# 18650Charger.net
KiCad netlist of a schematic drawn in EasyEDA Pro
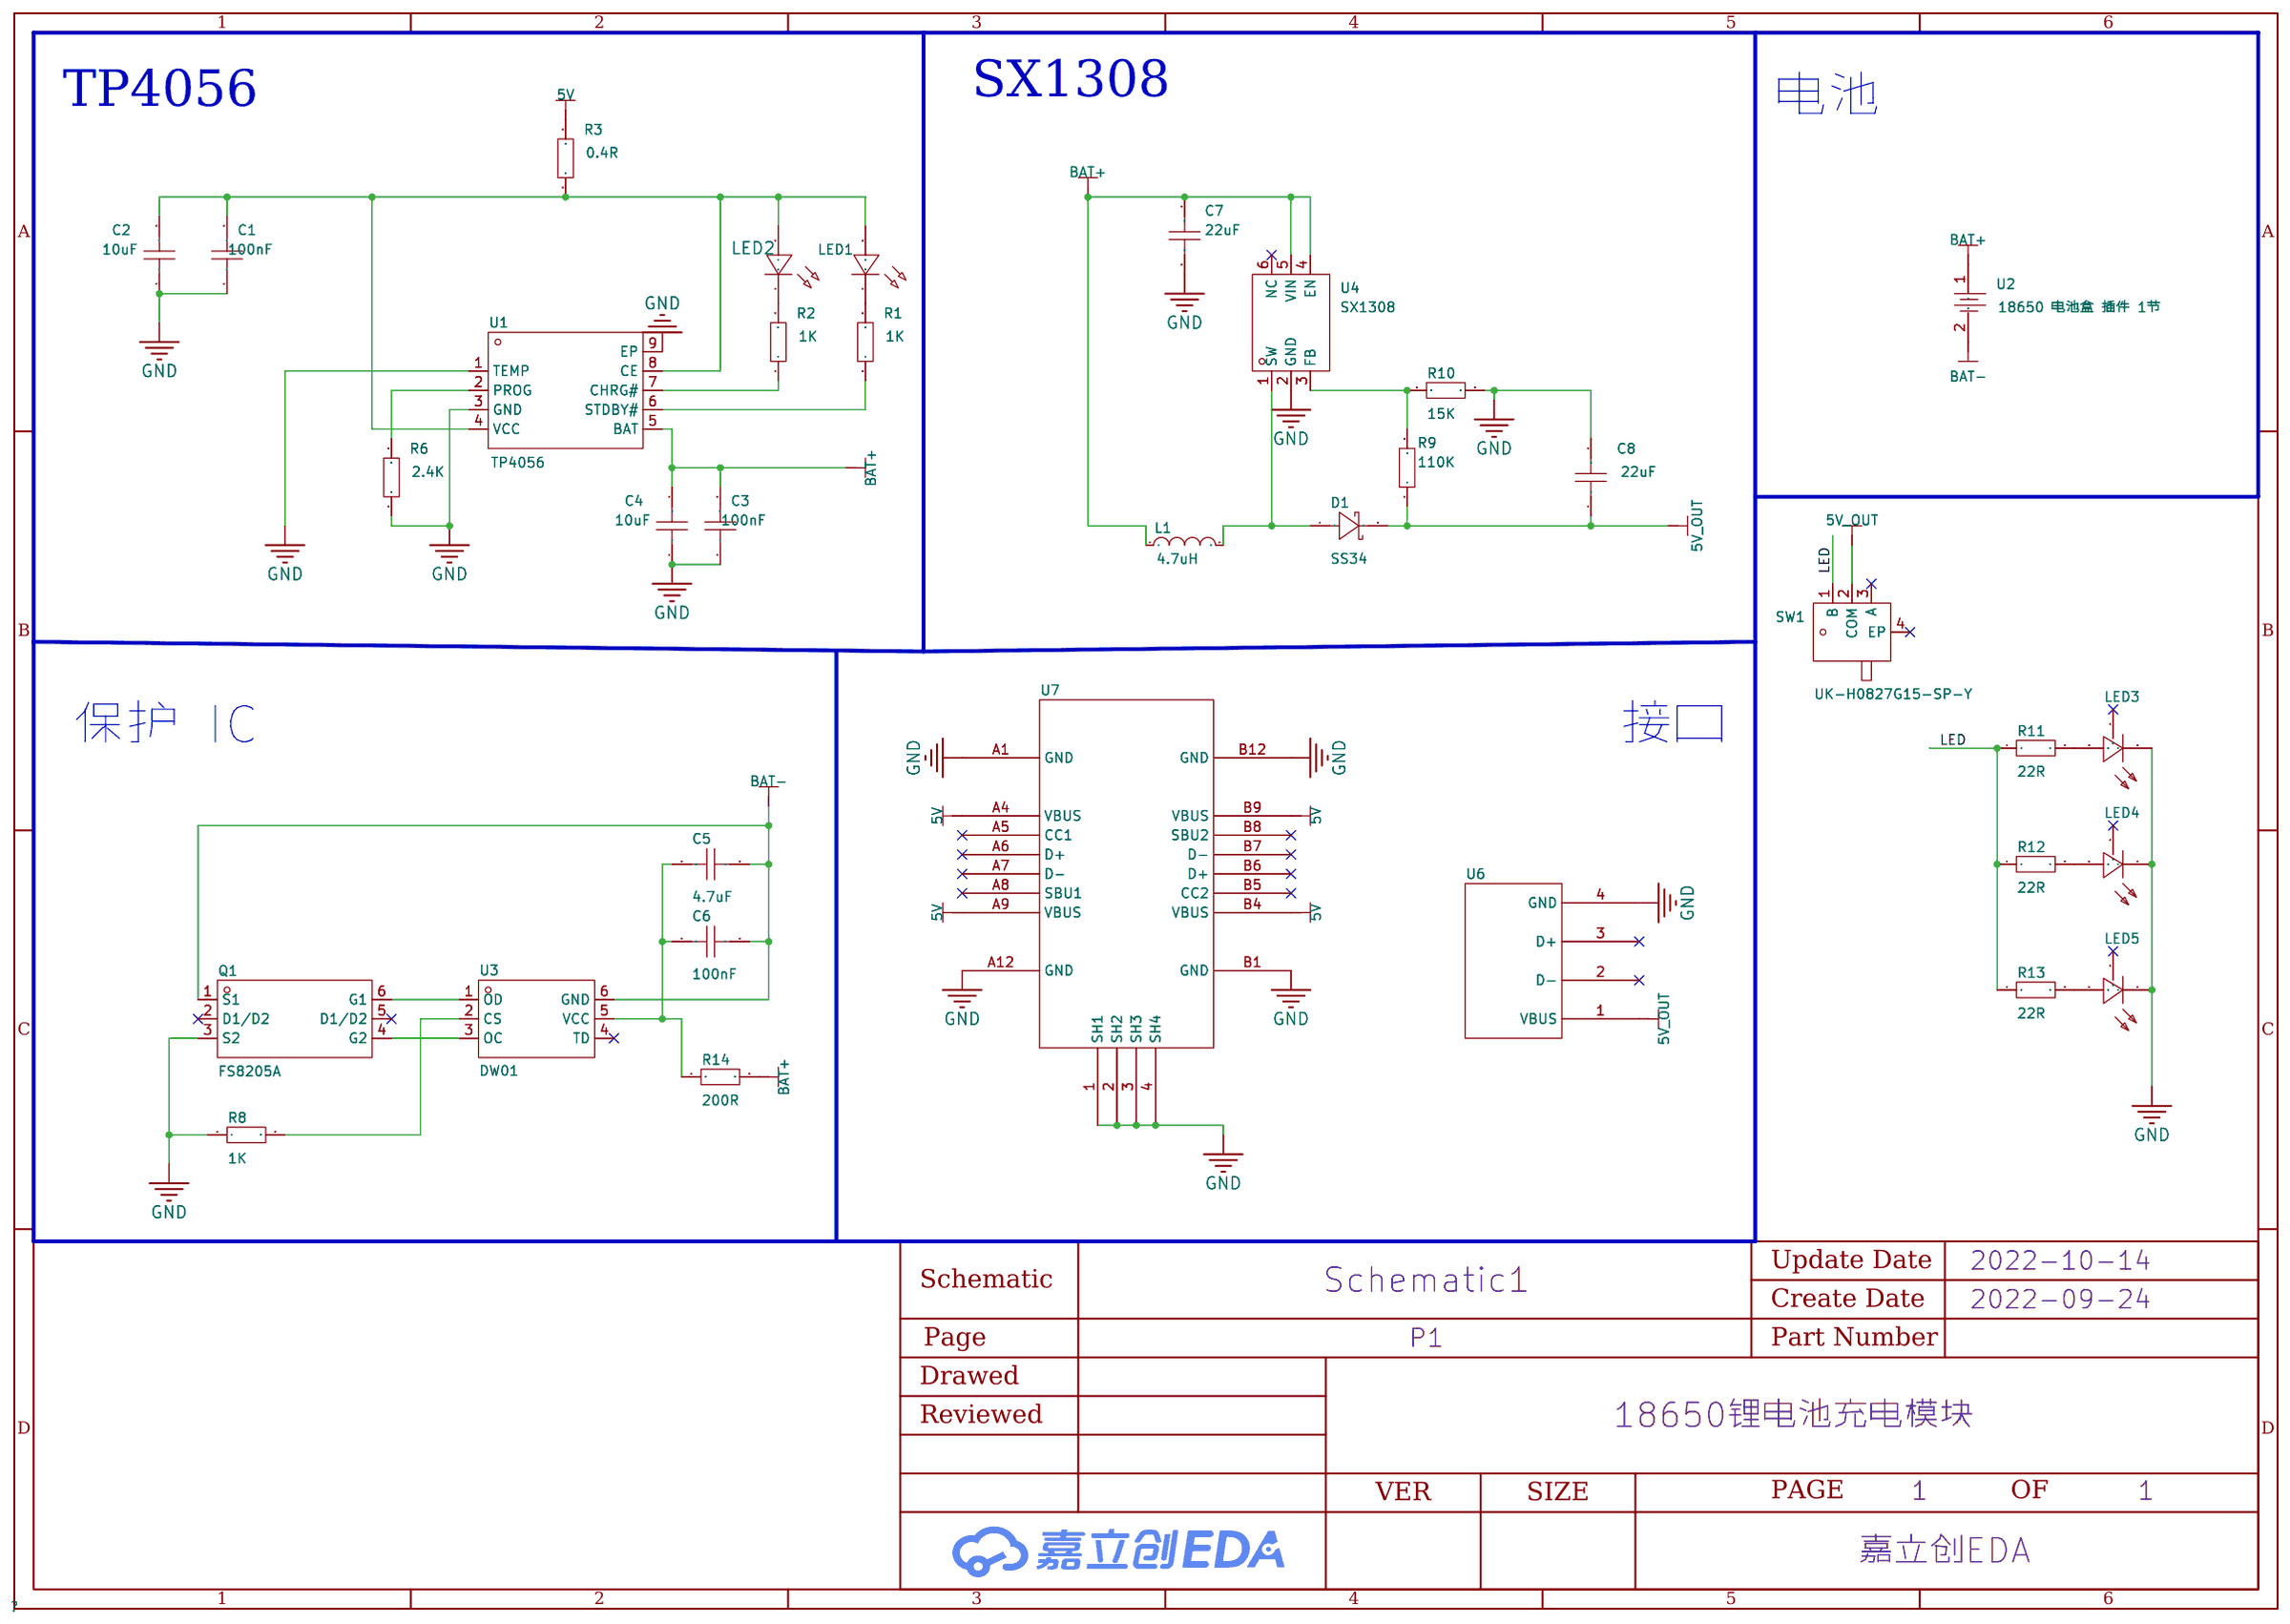
[diagram p0: schematic sheet]

(export (version "E")
  (design (tool "Eeschema 10.0.6"))
  (components
    (comp (ref "C1")
      (value "100nF")
      (footprint "easyedapro:C0805")
      (description "容值:100nF;精度:±10%;额定电压:50V;温度系数:X7R;")
      (libsource (lib "easyedapro") (part "C1210X7R475K630NT"))
    )
    (comp (ref "C2")
      (value "100nF")
      (footprint "easyedapro:C0805")
      (description "容值:100nF;精度:±10%;额定电压:50V;温度系数:X7R;")
      (libsource (lib "easyedapro") (part "C1210X7R475K630NT"))
    )
    (comp (ref "C3")
      (value "100nF")
      (footprint "easyedapro:C0805")
      (description "容值:100nF;精度:±10%;额定电压:50V;温度系数:X7R;")
      (libsource (lib "easyedapro") (part "C1210X7R475K630NT"))
    )
    (comp (ref "C4")
      (value "100nF")
      (footprint "easyedapro:C0805")
      (description "容值:100nF;精度:±10%;额定电压:50V;温度系数:X7R;")
      (libsource (lib "easyedapro") (part "C1210X7R475K630NT"))
    )
    (comp (ref "C5")
      (value "100nF")
      (footprint "easyedapro:C0805")
      (description "容值:100nF;精度:±10%;额定电压:50V;温度系数:X7R;")
      (libsource (lib "easyedapro") (part "C1210X7R475K630NT"))
    )
    (comp (ref "C6")
      (value "100nF")
      (footprint "easyedapro:C0805")
      (description "容值:100nF;精度:±10%;额定电压:50V;温度系数:X7R;")
      (libsource (lib "easyedapro") (part "C1210X7R475K630NT"))
    )
    (comp (ref "C7")
      (value "100nF")
      (footprint "easyedapro:C0805")
      (description "容值:100nF;精度:±10%;额定电压:50V;温度系数:X7R;")
      (libsource (lib "easyedapro") (part "C1210X7R475K630NT"))
    )
    (comp (ref "C8")
      (value "100nF")
      (footprint "easyedapro:C0805")
      (description "容值:100nF;精度:±10%;额定电压:50V;温度系数:X7R;")
      (libsource (lib "easyedapro") (part "C1210X7R475K630NT"))
    )
    (comp (ref "D1")
      (value "SS34")
      (footprint "easyedapro:SMA_L4.3-W2.5-LS5.0-FD")
      (description "二极管配置:独立式;直流反向耐压(Vr):40V;平均整流电流(Io):3A;正向压降(Vf):550mV@3A;反向电流(Ir):500A@40V;")
      (fields (field (name "Manufacturer") "Doeshare(德芯)"))
      (libsource (lib "easyedapro") (part "SS34_C2931787"))
    )
    (comp (ref "L1")
      (value "4.7uH")
      (footprint "easyedapro:IND-SMD_L7.4-W6.6")
      (fields
        (field (name "Manufacturer Part") "CKST0603-4.7uH/M")
        (field (name "Manufacturer") "CENKER(岑科)")
      )
      (libsource (lib "easyedapro") (part "CKST0603-4.7UH/M_C3002636"))
    )
    (comp (ref "LED1")
      (value "~")
      (footprint "easyedapro:LED0805-RD_RED")
      (libsource (lib "easyedapro") (part "LED_G"))
    )
    (comp (ref "LED2")
      (value "~")
      (footprint "easyedapro:LED0805-RD_RED")
      (libsource (lib "easyedapro") (part "LED_R"))
    )
    (comp (ref "LED3")
      (value "HL-A-5730D34W-S1-08-HR3(LY)")
      (footprint "easyedapro:LED-SMD_3P-L5.7-W3.0-RD")
      (fields (field (name "Manufacturer") "HONGLITRONIC(鸿利光电)"))
      (libsource (lib "easyedapro") (part "HL-A-5730D34W-S1-08-HR3(LY)_C210354"))
    )
    (comp (ref "LED4")
      (value "HL-A-5730D34W-S1-08-HR3(LY)")
      (footprint "easyedapro:LED-SMD_3P-L5.7-W3.0-RD")
      (fields (field (name "Manufacturer") "HONGLITRONIC(鸿利光电)"))
      (libsource (lib "easyedapro") (part "HL-A-5730D34W-S1-08-HR3(LY)_C210354"))
    )
    (comp (ref "LED5")
      (value "HL-A-5730D34W-S1-08-HR3(LY)")
      (footprint "easyedapro:LED-SMD_3P-L5.7-W3.0-RD")
      (fields (field (name "Manufacturer") "HONGLITRONIC(鸿利光电)"))
      (libsource (lib "easyedapro") (part "HL-A-5730D34W-S1-08-HR3(LY)_C210354"))
    )
    (comp (ref "Q1")
      (value "FS8205A")
      (footprint "easyedapro:SOT-23-6_L2.9-W1.6-P0.95-LS2.8-BR")
      (fields (field (name "Manufacturer") "TECH PUBLIC(台舟)"))
      (libsource (lib "easyedapro") (part "FS8205A_C2830320"))
    )
    (comp (ref "R1") (value "10K") (footprint "easyedapro:R0603") (libsource (lib "easyedapro") (part "电阻")))
    (comp (ref "R2") (value "10K") (footprint "easyedapro:R0603") (libsource (lib "easyedapro") (part "电阻")))
    (comp (ref "R3") (value "10K") (footprint "easyedapro:R0603") (libsource (lib "easyedapro") (part "电阻")))
    (comp (ref "R6") (value "10K") (footprint "easyedapro:R0603") (libsource (lib "easyedapro") (part "电阻")))
    (comp (ref "R8") (value "10K") (footprint "easyedapro:R0603") (libsource (lib "easyedapro") (part "电阻")))
    (comp (ref "R9") (value "10K") (footprint "easyedapro:R0603") (libsource (lib "easyedapro") (part "电阻")))
    (comp (ref "R10") (value "10K") (footprint "easyedapro:R0603") (libsource (lib "easyedapro") (part "电阻")))
    (comp (ref "R11") (value "10K") (footprint "easyedapro:R0603") (libsource (lib "easyedapro") (part "电阻")))
    (comp (ref "R12") (value "10K") (footprint "easyedapro:R0603") (libsource (lib "easyedapro") (part "电阻")))
    (comp (ref "R13") (value "10K") (footprint "easyedapro:R0603") (libsource (lib "easyedapro") (part "电阻")))
    (comp (ref "R14") (value "10K") (footprint "easyedapro:R0603") (libsource (lib "easyedapro") (part "电阻")))
    (comp (ref "SW1")
      (value "UK-H0827G15-SP-Y")
      (footprint "easyedapro:SW-SMD_UK-H0827G15-SP-Y")
      (description "电路结构:-;开关功能:-;额定电压 DC:-;触点额定电流:-;额定电压 AC:-;")
      (fields (field (name "Manufacturer") "USAKRO(美韩)"))
      (libsource (lib "easyedapro") (part "UK-H0827G15-SP-Y"))
    )
    (comp (ref "U1")
      (value "TP4056")
      (footprint "easyedapro:ESOP-8_L4.9-W3.9-P1.27-LS6.0-BL-EP")
      (fields (field (name "Manufacturer") "UMW(友台半导体)"))
      (libsource (lib "easyedapro") (part "TP4056_C725790"))
    )
    (comp (ref "U2")
      (value "18650 电池盒 插件 1节")
      (footprint "easyedapro:BAT-TH_18650-C9900004923")
      (libsource (lib "easyedapro") (part "18650 电池盒 插件 1节"))
    )
    (comp (ref "U3")
      (value "DW01")
      (footprint "easyedapro:SOT-23-6_L2.9-W1.6-P0.95-LS2.8-BR")
      (description "充电电池的类型:-;电池单元组数:-;最大充电电流:-;充满的电池组电压:-;最大供应电压:-;")
      (fields (field (name "Manufacturer") "HUASHUO(华朔)"))
      (libsource (lib "easyedapro") (part "DW01_C700964"))
    )
    (comp (ref "U4")
      (value "SX1308")
      (footprint "easyedapro:SOT-23-6_L2.9-W1.6-P0.95-LS2.8-BR")
      (description "功能类型:升压型;同步整流:否;输出通道数:1;拓扑结构:升压式;输入电压:2V~24V;输出电压:28V;输出电流(最大值):-;开关频率:1.2MHz;")
      (fields (field (name "Manufacturer") "SX(硕芯科技)"))
      (libsource (lib "easyedapro") (part "SX1308"))
    )
    (comp (ref "U6")
      (value "~")
      (footprint "easyedapro:USB-A Short")
      (libsource (lib "easyedapro") (part "USB-A Short"))
    )
    (comp (ref "U7")
      (value "~")
      (footprint "easyedapro:TypeC-16p")
      (libsource (lib "easyedapro") (part "Type C"))
    )
  )
  (nets
    (net (code "1") (name "/LED") (class "Default")
      (node (ref "R11") (pin "1") (pinfunction "1_1") (pintype "input"))
      (node (ref "R12") (pin "1") (pinfunction "1_1") (pintype "input"))
      (node (ref "R13") (pin "1") (pinfunction "1_1") (pintype "input"))
      (node (ref "SW1") (pin "1") (pinfunction "B_1") (pintype "input"))
    )
    (net (code "2") (name "5V") (class "Default")
      (node (ref "R3") (pin "2") (pinfunction "2_2") (pintype "input"))
      (node (ref "U7") (pin "A4") (pinfunction "VBUS_A4") (pintype "input"))
      (node (ref "U7") (pin "A9") (pinfunction "VBUS_A9") (pintype "input"))
      (node (ref "U7") (pin "B4") (pinfunction "VBUS_B4") (pintype "input"))
      (node (ref "U7") (pin "B9") (pinfunction "VBUS_B9") (pintype "input"))
    )
    (net (code "3") (name "5V_OUT") (class "Default")
      (node (ref "C8") (pin "1") (pinfunction "1_1") (pintype "input"))
      (node (ref "D1") (pin "2") (pinfunction "K_2") (pintype "input"))
      (node (ref "R9") (pin "1") (pinfunction "1_1") (pintype "input"))
      (node (ref "SW1") (pin "2") (pinfunction "COM_2") (pintype "input"))
      (node (ref "U6") (pin "1") (pinfunction "VBUS_1") (pintype "input"))
    )
    (net (code "4") (name "BAT+") (class "Default")
      (node (ref "C3") (pin "2") (pinfunction "2_2") (pintype "input"))
      (node (ref "C4") (pin "2") (pinfunction "2_2") (pintype "input"))
      (node (ref "C7") (pin "2") (pinfunction "2_2") (pintype "input"))
      (node (ref "L1") (pin "1") (pinfunction "1_1") (pintype "input"))
      (node (ref "R14") (pin "2") (pinfunction "2_2") (pintype "input"))
      (node (ref "U1") (pin "5") (pinfunction "BAT_5") (pintype "input"))
      (node (ref "U2") (pin "1") (pinfunction "1_1") (pintype "input"))
      (node (ref "U4") (pin "4") (pinfunction "EN_4") (pintype "input"))
      (node (ref "U4") (pin "5") (pinfunction "VIN_5") (pintype "input"))
    )
    (net (code "5") (name "BAT-") (class "Default")
      (node (ref "C5") (pin "2") (pinfunction "2_2") (pintype "input"))
      (node (ref "C6") (pin "2") (pinfunction "2_2") (pintype "input"))
      (node (ref "Q1") (pin "1") (pinfunction "S1_1") (pintype "input"))
      (node (ref "U2") (pin "2") (pinfunction "2_2") (pintype "input"))
      (node (ref "U3") (pin "6") (pinfunction "GND_6") (pintype "input"))
    )
    (net (code "6") (name "GND") (class "Default")
      (node (ref "C1") (pin "1") (pinfunction "1_1") (pintype "input"))
      (node (ref "C2") (pin "1") (pinfunction "1_1") (pintype "input"))
      (node (ref "C3") (pin "1") (pinfunction "1_1") (pintype "input"))
      (node (ref "C4") (pin "1") (pinfunction "1_1") (pintype "input"))
      (node (ref "C7") (pin "1") (pinfunction "1_1") (pintype "input"))
      (node (ref "C8") (pin "2") (pinfunction "2_2") (pintype "input"))
      (node (ref "LED3") (pin "1") (pinfunction "1_1") (pintype "input"))
      (node (ref "LED4") (pin "1") (pinfunction "1_1") (pintype "input"))
      (node (ref "LED5") (pin "1") (pinfunction "1_1") (pintype "input"))
      (node (ref "Q1") (pin "3") (pinfunction "S2_3") (pintype "input"))
      (node (ref "R10") (pin "2") (pinfunction "2_2") (pintype "input"))
      (node (ref "R6") (pin "1") (pinfunction "1_1") (pintype "input"))
      (node (ref "R8") (pin "1") (pinfunction "1_1") (pintype "input"))
      (node (ref "U1") (pin "1") (pinfunction "TEMP_1") (pintype "input"))
      (node (ref "U1") (pin "3") (pinfunction "GND_3") (pintype "input"))
      (node (ref "U1") (pin "9") (pinfunction "EP_9") (pintype "input"))
      (node (ref "U4") (pin "2") (pinfunction "GND_2") (pintype "input"))
      (node (ref "U6") (pin "4") (pinfunction "GND_4") (pintype "input"))
      (node (ref "U7") (pin "1") (pinfunction "SH1_1") (pintype "input"))
      (node (ref "U7") (pin "2") (pinfunction "SH2_2") (pintype "input"))
      (node (ref "U7") (pin "3") (pinfunction "SH3_3") (pintype "input"))
      (node (ref "U7") (pin "4") (pinfunction "SH4_4") (pintype "input"))
      (node (ref "U7") (pin "A1") (pinfunction "GND_A1") (pintype "input"))
      (node (ref "U7") (pin "A12") (pinfunction "GND_A12") (pintype "input"))
      (node (ref "U7") (pin "B1") (pinfunction "GND_B1") (pintype "input"))
      (node (ref "U7") (pin "B12") (pinfunction "GND_B12") (pintype "input"))
    )
    (net (code "7") (name "Net-(D1-A)") (class "Default")
      (node (ref "D1") (pin "1") (pinfunction "A_1") (pintype "input"))
      (node (ref "L1") (pin "2") (pinfunction "2_2") (pintype "input"))
      (node (ref "U4") (pin "1") (pinfunction "SW_1") (pintype "input"))
    )
    (net (code "8") (name "Net-(LED1-A)") (class "Default")
      (node (ref "C1") (pin "2") (pinfunction "2_2") (pintype "input"))
      (node (ref "C2") (pin "2") (pinfunction "2_2") (pintype "input"))
      (node (ref "LED1") (pin "2") (pinfunction "A_2") (pintype "input"))
      (node (ref "LED2") (pin "2") (pinfunction "A_2") (pintype "input"))
      (node (ref "R3") (pin "1") (pinfunction "1_1") (pintype "input"))
      (node (ref "U1") (pin "4") (pinfunction "VCC_4") (pintype "input"))
      (node (ref "U1") (pin "8") (pinfunction "CE_8") (pintype "input"))
    )
    (net (code "9") (name "Net-(LED1-C)") (class "Default")
      (node (ref "LED1") (pin "1") (pinfunction "C_1") (pintype "input"))
      (node (ref "R1") (pin "2") (pinfunction "2_2") (pintype "input"))
    )
    (net (code "10") (name "Net-(LED2-C)") (class "Default")
      (node (ref "LED2") (pin "1") (pinfunction "C_1") (pintype "input"))
      (node (ref "R2") (pin "2") (pinfunction "2_2") (pintype "input"))
    )
    (net (code "11") (name "Net-(LED3-Pad2)") (class "Default")
      (node (ref "LED3") (pin "2") (pinfunction "2_2") (pintype "input"))
      (node (ref "R11") (pin "2") (pinfunction "2_2") (pintype "input"))
    )
    (net (code "12") (name "Net-(LED4-Pad2)") (class "Default")
      (node (ref "LED4") (pin "2") (pinfunction "2_2") (pintype "input"))
      (node (ref "R12") (pin "2") (pinfunction "2_2") (pintype "input"))
    )
    (net (code "13") (name "Net-(LED5-Pad2)") (class "Default")
      (node (ref "LED5") (pin "2") (pinfunction "2_2") (pintype "input"))
      (node (ref "R13") (pin "2") (pinfunction "2_2") (pintype "input"))
    )
    (net (code "14") (name "Net-(Q1-G1)") (class "Default")
      (node (ref "Q1") (pin "6") (pinfunction "G1_6") (pintype "input"))
      (node (ref "U3") (pin "1") (pinfunction "OD_1") (pintype "input"))
    )
    (net (code "15") (name "Net-(Q1-G2)") (class "Default")
      (node (ref "Q1") (pin "4") (pinfunction "G2_4") (pintype "input"))
      (node (ref "U3") (pin "3") (pinfunction "OC_3") (pintype "input"))
    )
    (net (code "16") (name "Net-(U1-CHRG#)") (class "Default")
      (node (ref "R2") (pin "1") (pinfunction "1_1") (pintype "input"))
      (node (ref "U1") (pin "7") (pinfunction "CHRG#_7") (pintype "input"))
    )
    (net (code "17") (name "Net-(U1-PROG)") (class "Default")
      (node (ref "R6") (pin "2") (pinfunction "2_2") (pintype "input"))
      (node (ref "U1") (pin "2") (pinfunction "PROG_2") (pintype "input"))
    )
    (net (code "18") (name "Net-(U1-STDBY#)") (class "Default")
      (node (ref "R1") (pin "1") (pinfunction "1_1") (pintype "input"))
      (node (ref "U1") (pin "6") (pinfunction "STDBY#_6") (pintype "input"))
    )
    (net (code "19") (name "Net-(U3-CS)") (class "Default")
      (node (ref "R8") (pin "2") (pinfunction "2_2") (pintype "input"))
      (node (ref "U3") (pin "2") (pinfunction "CS_2") (pintype "input"))
    )
    (net (code "20") (name "Net-(U3-VCC)") (class "Default")
      (node (ref "C5") (pin "1") (pinfunction "1_1") (pintype "input"))
      (node (ref "C6") (pin "1") (pinfunction "1_1") (pintype "input"))
      (node (ref "R14") (pin "1") (pinfunction "1_1") (pintype "input"))
      (node (ref "U3") (pin "5") (pinfunction "VCC_5") (pintype "input"))
    )
    (net (code "21") (name "Net-(U4-FB)") (class "Default")
      (node (ref "R10") (pin "1") (pinfunction "1_1") (pintype "input"))
      (node (ref "R9") (pin "2") (pinfunction "2_2") (pintype "input"))
      (node (ref "U4") (pin "3") (pinfunction "FB_3") (pintype "input"))
    )
    (net (code "22") (name "unconnected-(LED3-Pad3)") (class "Default")
      (node (ref "LED3") (pin "3") (pinfunction "3_3") (pintype "input+no_connect"))
    )
    (net (code "23") (name "unconnected-(LED4-Pad3)") (class "Default")
      (node (ref "LED4") (pin "3") (pinfunction "3_3") (pintype "input+no_connect"))
    )
    (net (code "24") (name "unconnected-(LED5-Pad3)") (class "Default")
      (node (ref "LED5") (pin "3") (pinfunction "3_3") (pintype "input+no_connect"))
    )
    (net (code "25") (name "unconnected-(Q1-D1{slash}D2-Pad2)") (class "Default")
      (node (ref "Q1") (pin "2") (pinfunction "D1/D2_2") (pintype "input+no_connect"))
    )
    (net (code "26") (name "unconnected-(Q1-D1{slash}D2-Pad5)") (class "Default")
      (node (ref "Q1") (pin "5") (pinfunction "D1/D2_5") (pintype "input+no_connect"))
    )
    (net (code "27") (name "unconnected-(SW1-A-Pad3)") (class "Default")
      (node (ref "SW1") (pin "3") (pinfunction "A_3") (pintype "input+no_connect"))
    )
    (net (code "28") (name "unconnected-(SW1-EP-Pad4)") (class "Default")
      (node (ref "SW1") (pin "4") (pinfunction "EP_4") (pintype "input+no_connect"))
    )
    (net (code "29") (name "unconnected-(U3-TD-Pad4)") (class "Default")
      (node (ref "U3") (pin "4") (pinfunction "TD_4") (pintype "input+no_connect"))
    )
    (net (code "30") (name "unconnected-(U4-NC-Pad6)") (class "Default")
      (node (ref "U4") (pin "6") (pinfunction "NC_6") (pintype "input+no_connect"))
    )
    (net (code "31") (name "unconnected-(U6-D+-Pad3)") (class "Default")
      (node (ref "U6") (pin "3") (pinfunction "D+_3") (pintype "input+no_connect"))
    )
    (net (code "32") (name "unconnected-(U6-D--Pad2)") (class "Default")
      (node (ref "U6") (pin "2") (pinfunction "D-_2") (pintype "input+no_connect"))
    )
    (net (code "33") (name "unconnected-(U7-CC1-PadA5)") (class "Default")
      (node (ref "U7") (pin "A5") (pinfunction "CC1_A5") (pintype "input+no_connect"))
    )
    (net (code "34") (name "unconnected-(U7-CC2-PadB5)") (class "Default")
      (node (ref "U7") (pin "B5") (pinfunction "CC2_B5") (pintype "input+no_connect"))
    )
    (net (code "35") (name "unconnected-(U7-D+-PadA6)") (class "Default")
      (node (ref "U7") (pin "A6") (pinfunction "D+_A6") (pintype "input+no_connect"))
    )
    (net (code "36") (name "unconnected-(U7-D+-PadB6)") (class "Default")
      (node (ref "U7") (pin "B6") (pinfunction "D+_B6") (pintype "input+no_connect"))
    )
    (net (code "37") (name "unconnected-(U7-D--PadA7)") (class "Default")
      (node (ref "U7") (pin "A7") (pinfunction "D-_A7") (pintype "input+no_connect"))
    )
    (net (code "38") (name "unconnected-(U7-D--PadB7)") (class "Default")
      (node (ref "U7") (pin "B7") (pinfunction "D-_B7") (pintype "input+no_connect"))
    )
    (net (code "39") (name "unconnected-(U7-SBU1-PadA8)") (class "Default")
      (node (ref "U7") (pin "A8") (pinfunction "SBU1_A8") (pintype "input+no_connect"))
    )
    (net (code "40") (name "unconnected-(U7-SBU2-PadB8)") (class "Default")
      (node (ref "U7") (pin "B8") (pinfunction "SBU2_B8") (pintype "input+no_connect"))
    )
  )
)
